# Schematic.net
KiCad netlist of a schematic drawn in Altium Designer
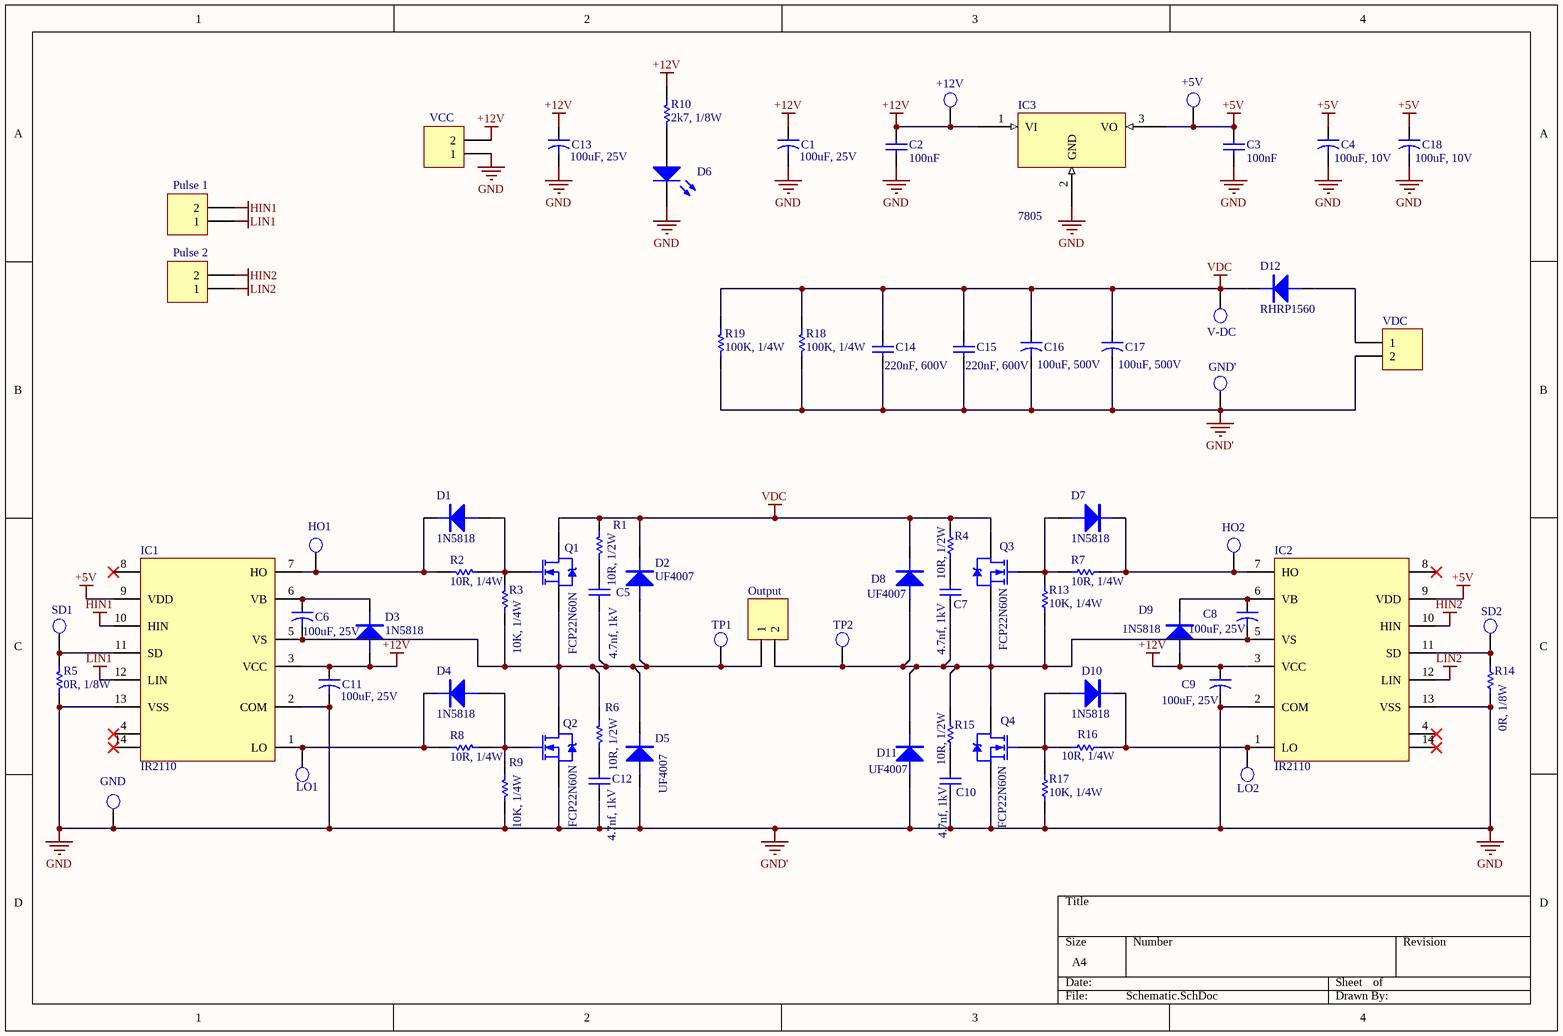
[diagram p0: Schematic.SchDoc]

(export (version "E")
  (design (tool "Eeschema 10.0.6"))
  (components
    (comp (ref "+5V") (value "+5V") (footprint "TPTHD_B_WHT") (libsource (lib "JDEVS-SCH") (part "TP")))
    (comp (ref "+12V") (value "+12V") (footprint "TPTHD_B_WHT") (libsource (lib "JDEVS-SCH") (part "TP")))
    (comp (ref "C1")
      (value "100uF, 25V")
      (footprint "C_EL_6X11")
      (description "200V, 330uF")
      (libsource (lib "Miscellaneous Devices") (part "Cap2"))
    )
    (comp (ref "C2")
      (value "100nF")
      (footprint "C_PLY_6X2_5")
      (description "Capacitor")
      (libsource (lib "Miscellaneous Devices") (part "Cap"))
    )
    (comp (ref "C3")
      (value "100nF")
      (footprint "C_PLY_6X2_5")
      (description "Capacitor")
      (libsource (lib "Miscellaneous Devices") (part "Cap"))
    )
    (comp (ref "C4")
      (value "100uF, 10V")
      (footprint "C_EL_5X11")
      (description "200V, 330uF")
      (libsource (lib "Miscellaneous Devices") (part "Cap2"))
    )
    (comp (ref "C5")
      (value "4.7nf, 1kV")
      (footprint "RAD0.2-1")
      (libsource (lib "Miscellaneous Devices") (part "Cap"))
    )
    (comp (ref "C6")
      (value "100uF, 25V")
      (footprint "C_EL_6X11")
      (description "200V, 330uF")
      (libsource (lib "Miscellaneous Devices") (part "Cap2"))
    )
    (comp (ref "C7")
      (value "4.7nf, 1kV")
      (footprint "RAD0.2-1")
      (libsource (lib "Miscellaneous Devices") (part "Cap"))
    )
    (comp (ref "C8")
      (value "100uF, 25V")
      (footprint "C_EL_6X11")
      (description "200V, 330uF")
      (libsource (lib "") (part "Cap2_1"))
    )
    (comp (ref "C9")
      (value "100uF, 25V")
      (footprint "C_EL_6X11")
      (description "200V, 330uF")
      (libsource (lib "") (part "Cap2_1"))
    )
    (comp (ref "C10")
      (value "4.7nf, 1kV")
      (footprint "RAD0.2-1")
      (libsource (lib "Miscellaneous Devices") (part "Cap"))
    )
    (comp (ref "C11")
      (value "100uF, 25V")
      (footprint "C_EL_6X11")
      (description "200V, 330uF")
      (libsource (lib "Miscellaneous Devices") (part "Cap2"))
    )
    (comp (ref "C12")
      (value "4.7nf, 1kV")
      (footprint "RAD0.2-1")
      (libsource (lib "Miscellaneous Devices") (part "Cap"))
    )
    (comp (ref "C13")
      (value "100uF, 25V")
      (footprint "C_EL_6X11")
      (description "200V, 330uF")
      (libsource (lib "Miscellaneous Devices") (part "Cap2"))
    )
    (comp (ref "C14")
      (value "220nF, 600V")
      (footprint "CAP-pitch15")
      (libsource (lib "Miscellaneous Devices") (part "Cap"))
    )
    (comp (ref "C15")
      (value "220nF, 600V")
      (footprint "CAP-pitch15")
      (libsource (lib "Miscellaneous Devices") (part "Cap"))
    )
    (comp (ref "C16")
      (value "100uF, 500V")
      (footprint "C_EL_18X35")
      (description "500HXW100MEFR18X40")
      (libsource (lib "Miscellaneous Devices") (part "Cap2"))
    )
    (comp (ref "C17")
      (value "100uF, 500V")
      (footprint "C_EL_18X35")
      (description "500HXW100MEFR18X40")
      (libsource (lib "Miscellaneous Devices") (part "Cap2"))
    )
    (comp (ref "C18")
      (value "100uF, 10V")
      (footprint "C_EL_5X11")
      (description "200V, 330uF")
      (libsource (lib "Miscellaneous Devices") (part "Cap2"))
    )
    (comp (ref "D1")
      (value "1N5818")
      (footprint "D_AX04_DO41")
      (fields (field (name "MANUFACTURER") "Comchip Technology"))
      (libsource (lib "JDEVS-SCH") (part "DIODE5"))
    )
    (comp (ref "D2")
      (value "UF4007")
      (footprint "D_AX04_DO41")
      (fields (field (name "MANUFACTURER") "Comchip Technology"))
      (libsource (lib "JDEVS-SCH") (part "DIODE5"))
    )
    (comp (ref "D3")
      (value "1N5818")
      (footprint "D_AX04_DO41")
      (fields (field (name "MANUFACTURER") "Comchip Technology"))
      (libsource (lib "JDEVS-SCH") (part "DIODE5"))
    )
    (comp (ref "D4")
      (value "1N5818")
      (footprint "D_AX04_DO41")
      (fields (field (name "MANUFACTURER") "Comchip Technology"))
      (libsource (lib "JDEVS-SCH") (part "DIODE5"))
    )
    (comp (ref "D5")
      (value "UF4007")
      (footprint "D_AX04_DO41")
      (fields (field (name "MANUFACTURER") "Comchip Technology"))
      (libsource (lib "JDEVS-SCH") (part "DIODE5"))
    )
    (comp (ref "D6")
      (value "LED RED")
      (footprint "LED3MM")
      (description "Typical INFRARED GaAs LED")
      (libsource (lib "Miscellaneous Devices") (part "LED0"))
    )
    (comp (ref "D7")
      (value "1N5818")
      (footprint "D_AX04_DO41")
      (fields (field (name "MANUFACTURER") "Comchip Technology"))
      (libsource (lib "JDEVS-SCH") (part "DIODE5"))
    )
    (comp (ref "D8")
      (value "UF4007")
      (footprint "D_AX04_DO41")
      (fields (field (name "MANUFACTURER") "Comchip Technology"))
      (libsource (lib "JDEVS-SCH") (part "DIODE5"))
    )
    (comp (ref "D9")
      (value "1N5818")
      (footprint "D_AX04_DO41")
      (fields (field (name "MANUFACTURER") "Comchip Technology"))
      (libsource (lib "JDEVS-SCH") (part "DIODE5"))
    )
    (comp (ref "D10")
      (value "1N5818")
      (footprint "D_AX04_DO41")
      (fields (field (name "MANUFACTURER") "Comchip Technology"))
      (libsource (lib "JDEVS-SCH") (part "DIODE5"))
    )
    (comp (ref "D11")
      (value "UF4007")
      (footprint "D_AX04_DO41")
      (fields (field (name "MANUFACTURER") "Comchip Technology"))
      (libsource (lib "JDEVS-SCH") (part "DIODE5"))
    )
    (comp (ref "D12") (value "RHRP1560") (footprint "TO220_21") (libsource (lib "") (part "DIODE5_1")))
    (comp (ref "GND") (value "GND") (footprint "TPTHD_B_WHT") (libsource (lib "JDEVS-SCH") (part "TP")))
    (comp (ref "GND'") (value "HO") (footprint "TPTHD_B_WHT") (libsource (lib "JDEVS-SCH") (part "TP")))
    (comp (ref "HO1") (value "HO") (footprint "TPTHD_B_WHT") (libsource (lib "JDEVS-SCH") (part "TP")))
    (comp (ref "HO2") (value "HO") (footprint "TPTHD_B_WHT") (libsource (lib "JDEVS-SCH") (part "TP")))
    (comp (ref "IC1") (value "IR2110") (footprint "DIP_14") (libsource (lib "") (part "IR2110_1")))
    (comp (ref "IC2") (value "IR2110") (footprint "DIP_14") (libsource (lib "JDEVS-SCH") (part "IR2110")))
    (comp (ref "IC3") (value "7805") (footprint "TO220_3") (libsource (lib "JDEVS-SCH") (part "7805")))
    (comp (ref "LO1") (value "LO") (footprint "TPTHD_B_WHT") (libsource (lib "JDEVS-SCH") (part "TP")))
    (comp (ref "LO2") (value "LO") (footprint "TPTHD_B_WHT") (libsource (lib "JDEVS-SCH") (part "TP")))
    (comp (ref "Output")
      (value "Output")
      (footprint "TBG_2")
      (description "Header, 2-Pin")
      (libsource (lib "") (part "Header 2_1"))
    )
    (comp (ref "Pulse 1")
      (value "~")
      (footprint "TBG_2")
      (description "Header, 2-Pin")
      (libsource (lib "Miscellaneous Connectors") (part "Header 2"))
    )
    (comp (ref "Pulse 2")
      (value "~")
      (footprint "TBG_2")
      (description "Header, 2-Pin")
      (libsource (lib "Miscellaneous Connectors") (part "Header 2"))
    )
    (comp (ref "Q1")
      (value "FCP22N60N")
      (footprint "TO220_32")
      (description "N-Channel Power MOSFET")
      (libsource (lib "Miscellaneous Devices") (part "NMOS-2"))
    )
    (comp (ref "Q2")
      (value "FCP22N60N")
      (footprint "TO220_32")
      (description "N-Channel Power MOSFET")
      (libsource (lib "Miscellaneous Devices") (part "NMOS-2"))
    )
    (comp (ref "Q3")
      (value "FCP22N60N")
      (footprint "TO220_32")
      (description "N-Channel Power MOSFET")
      (libsource (lib "Miscellaneous Devices") (part "NMOS-2"))
    )
    (comp (ref "Q4")
      (value "FCP22N60N")
      (footprint "TO220_32")
      (description "N-Channel Power MOSFET")
      (libsource (lib "Miscellaneous Devices") (part "NMOS-2"))
    )
    (comp (ref "R1")
      (value "10R, 1/2W")
      (footprint "R05W_AX05")
      (description "Resistor")
      (libsource (lib "Miscellaneous Devices") (part "Res1"))
    )
    (comp (ref "R2")
      (value "10R, 1/4W")
      (footprint "R025W_AX04")
      (description "Resistor")
      (libsource (lib "Miscellaneous Devices") (part "Res1"))
    )
    (comp (ref "R3")
      (value "10K, 1/4W")
      (footprint "R025W_AX04")
      (description "Resistor")
      (libsource (lib "Miscellaneous Devices") (part "Res1"))
    )
    (comp (ref "R4")
      (value "10R, 1/2W")
      (footprint "R05W_AX05")
      (description "Resistor")
      (libsource (lib "Miscellaneous Devices") (part "Res1"))
    )
    (comp (ref "R5")
      (value "0R, 1/8W")
      (footprint "R0125W_AX025")
      (description "Resistor")
      (libsource (lib "Miscellaneous Devices") (part "Res1"))
    )
    (comp (ref "R6")
      (value "10R, 1/2W")
      (footprint "R05W_AX05")
      (description "Resistor")
      (libsource (lib "Miscellaneous Devices") (part "Res1"))
    )
    (comp (ref "R7")
      (value "10R, 1/4W")
      (footprint "R025W_AX04")
      (description "Resistor")
      (libsource (lib "Miscellaneous Devices") (part "Res1"))
    )
    (comp (ref "R8")
      (value "10R, 1/4W")
      (footprint "R025W_AX04")
      (description "Resistor")
      (libsource (lib "Miscellaneous Devices") (part "Res1"))
    )
    (comp (ref "R9")
      (value "10K, 1/4W")
      (footprint "R025W_AX04")
      (description "Resistor")
      (libsource (lib "Miscellaneous Devices") (part "Res1"))
    )
    (comp (ref "R10")
      (value "2k7, 1/8W")
      (footprint "R0125W_AX025")
      (description "Resistor")
      (libsource (lib "Miscellaneous Devices") (part "Res1"))
    )
    (comp (ref "R13")
      (value "10K, 1/4W")
      (footprint "R025W_AX04")
      (description "Resistor")
      (libsource (lib "Miscellaneous Devices") (part "Res1"))
    )
    (comp (ref "R14")
      (value "0R, 1/8W")
      (footprint "R0125W_AX025")
      (description "Resistor")
      (libsource (lib "Miscellaneous Devices") (part "Res1"))
    )
    (comp (ref "R15")
      (value "10R, 1/2W")
      (footprint "R05W_AX05")
      (description "Resistor")
      (libsource (lib "Miscellaneous Devices") (part "Res1"))
    )
    (comp (ref "R16")
      (value "10R, 1/4W")
      (footprint "R025W_AX04")
      (description "Resistor")
      (libsource (lib "Miscellaneous Devices") (part "Res1"))
    )
    (comp (ref "R17")
      (value "10K, 1/4W")
      (footprint "R025W_AX04")
      (description "Resistor")
      (libsource (lib "Miscellaneous Devices") (part "Res1"))
    )
    (comp (ref "R18")
      (value "100K, 1/4W")
      (footprint "R025W_AX04")
      (description "Resistor")
      (libsource (lib "Miscellaneous Devices") (part "Res1"))
    )
    (comp (ref "R19")
      (value "100K, 1/4W")
      (footprint "R025W_AX04")
      (description "Resistor")
      (libsource (lib "Miscellaneous Devices") (part "Res1"))
    )
    (comp (ref "SD1") (value "SD") (footprint "TPTHD_B_WHT") (libsource (lib "JDEVS-SCH") (part "TP")))
    (comp (ref "SD2") (value "SD") (footprint "TPTHD_B_WHT") (libsource (lib "JDEVS-SCH") (part "TP")))
    (comp (ref "TP1") (value "HO") (footprint "TPTHD_B_WHT") (libsource (lib "JDEVS-SCH") (part "TP")))
    (comp (ref "TP2") (value "HO") (footprint "TPTHD_B_WHT") (libsource (lib "JDEVS-SCH") (part "TP")))
    (comp (ref "V-DC") (value "HO") (footprint "TPTHD_B_WHT") (libsource (lib "JDEVS-SCH") (part "TP")))
    (comp (ref "VCC")
      (value "~")
      (footprint "TBG_2")
      (description "Header, 2-Pin")
      (libsource (lib "Miscellaneous Connectors") (part "Header 2"))
    )
    (comp (ref "VDC")
      (value "~")
      (footprint "TBG_2")
      (description "Header, 2-Pin")
      (libsource (lib "") (part "Header 2_2"))
    )
  )
  (nets
    (net (code "1") (name "+5V") (class "Default")
      (node (ref "+5V") (pin "1") (pinfunction "1_1") (pintype "passive"))
      (node (ref "C18") (pin "1") (pinfunction "1_1") (pintype "passive"))
      (node (ref "C3") (pin "2") (pinfunction "2_2") (pintype "passive"))
      (node (ref "C4") (pin "1") (pinfunction "1_1") (pintype "passive"))
      (node (ref "IC1") (pin "9") (pinfunction "VDD_9") (pintype "passive"))
      (node (ref "IC2") (pin "9") (pinfunction "VDD_9") (pintype "passive"))
      (node (ref "IC3") (pin "3") (pinfunction "VO_3") (pintype "input"))
    )
    (net (code "2") (name "+12V") (class "Default")
      (node (ref "+12V") (pin "1") (pinfunction "1_1") (pintype "passive"))
      (node (ref "C1") (pin "1") (pinfunction "1_1") (pintype "passive"))
      (node (ref "C11") (pin "1") (pinfunction "1_1") (pintype "passive"))
      (node (ref "C13") (pin "1") (pinfunction "1_1") (pintype "passive"))
      (node (ref "C2") (pin "2") (pinfunction "2_2") (pintype "passive"))
      (node (ref "C9") (pin "1") (pinfunction "1_1") (pintype "passive"))
      (node (ref "D3") (pin "1") (pinfunction "1_1") (pintype "passive"))
      (node (ref "D9") (pin "1") (pinfunction "1_1") (pintype "passive"))
      (node (ref "IC1") (pin "3") (pinfunction "VCC_3") (pintype "passive"))
      (node (ref "IC2") (pin "3") (pinfunction "VCC_3") (pintype "passive"))
      (node (ref "IC3") (pin "1") (pinfunction "VI_1") (pintype "input"))
      (node (ref "R10") (pin "1") (pinfunction "1_1") (pintype "passive"))
      (node (ref "VCC") (pin "2") (pinfunction "2_2") (pintype "passive"))
    )
    (net (code "3") (name "GND") (class "Default")
      (node (ref "C1") (pin "2") (pinfunction "2_2") (pintype "passive"))
      (node (ref "C10") (pin "2") (pinfunction "2_2") (pintype "passive"))
      (node (ref "C11") (pin "2") (pinfunction "2_2") (pintype "passive"))
      (node (ref "C12") (pin "2") (pinfunction "2_2") (pintype "passive"))
      (node (ref "C13") (pin "2") (pinfunction "2_2") (pintype "passive"))
      (node (ref "C14") (pin "2") (pinfunction "2_2") (pintype "passive"))
      (node (ref "C15") (pin "2") (pinfunction "2_2") (pintype "passive"))
      (node (ref "C16") (pin "2") (pinfunction "2_2") (pintype "passive"))
      (node (ref "C17") (pin "2") (pinfunction "2_2") (pintype "passive"))
      (node (ref "C18") (pin "2") (pinfunction "2_2") (pintype "passive"))
      (node (ref "C2") (pin "1") (pinfunction "1_1") (pintype "passive"))
      (node (ref "C3") (pin "1") (pinfunction "1_1") (pintype "passive"))
      (node (ref "C4") (pin "2") (pinfunction "2_2") (pintype "passive"))
      (node (ref "C9") (pin "2") (pinfunction "2_2") (pintype "passive"))
      (node (ref "D11") (pin "1") (pinfunction "1_1") (pintype "passive"))
      (node (ref "D5") (pin "1") (pinfunction "1_1") (pintype "passive"))
      (node (ref "D6") (pin "2") (pinfunction "K_2") (pintype "passive"))
      (node (ref "GND") (pin "1") (pinfunction "1_1") (pintype "passive"))
      (node (ref "GND'") (pin "1") (pinfunction "1_1") (pintype "passive"))
      (node (ref "IC1") (pin "13") (pinfunction "VSS_13") (pintype "passive"))
      (node (ref "IC1") (pin "2") (pinfunction "COM_2") (pintype "passive"))
      (node (ref "IC2") (pin "13") (pinfunction "VSS_13") (pintype "passive"))
      (node (ref "IC2") (pin "2") (pinfunction "COM_2") (pintype "passive"))
      (node (ref "IC3") (pin "2") (pinfunction "GND_2") (pintype "input"))
      (node (ref "Q2") (pin "3") (pinfunction "S_3") (pintype "passive"))
      (node (ref "Q4") (pin "3") (pinfunction "S_3") (pintype "passive"))
      (node (ref "R14") (pin "1") (pinfunction "1_1") (pintype "passive"))
      (node (ref "R17") (pin "2") (pinfunction "2_2") (pintype "passive"))
      (node (ref "R18") (pin "1") (pinfunction "1_1") (pintype "passive"))
      (node (ref "R19") (pin "1") (pinfunction "1_1") (pintype "passive"))
      (node (ref "R5") (pin "1") (pinfunction "1_1") (pintype "passive"))
      (node (ref "R9") (pin "2") (pinfunction "2_2") (pintype "passive"))
      (node (ref "VCC") (pin "1") (pinfunction "1_1") (pintype "passive"))
      (node (ref "VDC") (pin "2") (pinfunction "2_2") (pintype "passive"))
    )
    (net (code "4") (name "HIN1") (class "Default")
      (node (ref "IC1") (pin "10") (pinfunction "HIN_10") (pintype "passive"))
      (node (ref "Pulse 1") (pin "2") (pinfunction "2_2") (pintype "passive"))
    )
    (net (code "5") (name "HIN2") (class "Default")
      (node (ref "IC2") (pin "10") (pinfunction "HIN_10") (pintype "passive"))
      (node (ref "Pulse 2") (pin "2") (pinfunction "2_2") (pintype "passive"))
    )
    (net (code "6") (name "LIN1") (class "Default")
      (node (ref "IC1") (pin "12") (pinfunction "LIN_12") (pintype "power_in"))
      (node (ref "Pulse 1") (pin "1") (pinfunction "1_1") (pintype "passive"))
    )
    (net (code "7") (name "LIN2") (class "Default")
      (node (ref "IC2") (pin "12") (pinfunction "LIN_12") (pintype "power_in"))
      (node (ref "Pulse 2") (pin "1") (pinfunction "1_1") (pintype "passive"))
    )
    (net (code "8") (name "Net-(C5-Pad1)") (class "Default")
      (node (ref "C5") (pin "1") (pinfunction "1_1") (pintype "passive"))
      (node (ref "R1") (pin "2") (pinfunction "2_2") (pintype "passive"))
    )
    (net (code "9") (name "Net-(C7-Pad1)") (class "Default")
      (node (ref "C7") (pin "1") (pinfunction "1_1") (pintype "passive"))
      (node (ref "R4") (pin "2") (pinfunction "2_2") (pintype "passive"))
    )
    (net (code "10") (name "Net-(C10-Pad1)") (class "Default")
      (node (ref "C10") (pin "1") (pinfunction "1_1") (pintype "passive"))
      (node (ref "R15") (pin "2") (pinfunction "2_2") (pintype "passive"))
    )
    (net (code "11") (name "Net-(C12-Pad1)") (class "Default")
      (node (ref "C12") (pin "1") (pinfunction "1_1") (pintype "passive"))
      (node (ref "R6") (pin "2") (pinfunction "2_2") (pintype "passive"))
    )
    (net (code "12") (name "Net-(D6-A)") (class "Default")
      (node (ref "D6") (pin "1") (pinfunction "A_1") (pintype "passive"))
      (node (ref "R10") (pin "2") (pinfunction "2_2") (pintype "passive"))
    )
    (net (code "13") (name "Net-(D12-1)") (class "Default")
      (node (ref "D12") (pin "2") (pinfunction "1_2") (pintype "passive"))
      (node (ref "VDC") (pin "1") (pinfunction "1_1") (pintype "passive"))
    )
    (net (code "14") (name "Net-(IC1-HO)") (class "Default")
      (node (ref "D1") (pin "2") (pinfunction "2_2") (pintype "passive"))
      (node (ref "HO1") (pin "1") (pinfunction "1_1") (pintype "passive"))
      (node (ref "IC1") (pin "7") (pinfunction "HO_7") (pintype "passive"))
      (node (ref "R2") (pin "1") (pinfunction "1_1") (pintype "passive"))
    )
    (net (code "15") (name "Net-(IC1-LO)") (class "Default")
      (node (ref "D4") (pin "2") (pinfunction "2_2") (pintype "passive"))
      (node (ref "IC1") (pin "1") (pinfunction "LO_1") (pintype "passive"))
      (node (ref "LO1") (pin "1") (pinfunction "1_1") (pintype "passive"))
      (node (ref "R8") (pin "1") (pinfunction "1_1") (pintype "passive"))
    )
    (net (code "16") (name "Net-(IC1-SD)") (class "Default")
      (node (ref "IC1") (pin "11") (pinfunction "SD_11") (pintype "power_in"))
      (node (ref "R5") (pin "2") (pinfunction "2_2") (pintype "passive"))
      (node (ref "SD1") (pin "1") (pinfunction "1_1") (pintype "passive"))
    )
    (net (code "17") (name "Net-(IC1-VB)") (class "Default")
      (node (ref "C6") (pin "1") (pinfunction "1_1") (pintype "passive"))
      (node (ref "D3") (pin "2") (pinfunction "2_2") (pintype "passive"))
      (node (ref "IC1") (pin "6") (pinfunction "VB_6") (pintype "passive"))
    )
    (net (code "18") (name "Net-(IC1-VS)") (class "Default")
      (node (ref "C5") (pin "2") (pinfunction "2_2") (pintype "passive"))
      (node (ref "C6") (pin "2") (pinfunction "2_2") (pintype "passive"))
      (node (ref "D2") (pin "1") (pinfunction "1_1") (pintype "passive"))
      (node (ref "D5") (pin "2") (pinfunction "2_2") (pintype "passive"))
      (node (ref "IC1") (pin "5") (pinfunction "VS_5") (pintype "passive"))
      (node (ref "Output") (pin "1") (pinfunction "1_1") (pintype "passive"))
      (node (ref "Q1") (pin "3") (pinfunction "S_3") (pintype "passive"))
      (node (ref "Q2") (pin "2") (pinfunction "D_2") (pintype "passive"))
      (node (ref "R3") (pin "2") (pinfunction "2_2") (pintype "passive"))
      (node (ref "R6") (pin "1") (pinfunction "1_1") (pintype "passive"))
      (node (ref "TP1") (pin "1") (pinfunction "1_1") (pintype "passive"))
    )
    (net (code "19") (name "Net-(IC2-HO)") (class "Default")
      (node (ref "D7") (pin "2") (pinfunction "2_2") (pintype "passive"))
      (node (ref "HO2") (pin "1") (pinfunction "1_1") (pintype "passive"))
      (node (ref "IC2") (pin "7") (pinfunction "HO_7") (pintype "passive"))
      (node (ref "R7") (pin "1") (pinfunction "1_1") (pintype "passive"))
    )
    (net (code "20") (name "Net-(IC2-LO)") (class "Default")
      (node (ref "D10") (pin "2") (pinfunction "2_2") (pintype "passive"))
      (node (ref "IC2") (pin "1") (pinfunction "LO_1") (pintype "passive"))
      (node (ref "LO2") (pin "1") (pinfunction "1_1") (pintype "passive"))
      (node (ref "R16") (pin "1") (pinfunction "1_1") (pintype "passive"))
    )
    (net (code "21") (name "Net-(IC2-SD)") (class "Default")
      (node (ref "IC2") (pin "11") (pinfunction "SD_11") (pintype "power_in"))
      (node (ref "R14") (pin "2") (pinfunction "2_2") (pintype "passive"))
      (node (ref "SD2") (pin "1") (pinfunction "1_1") (pintype "passive"))
    )
    (net (code "22") (name "Net-(IC2-VB)") (class "Default")
      (node (ref "C8") (pin "1") (pinfunction "1_1") (pintype "passive"))
      (node (ref "D9") (pin "2") (pinfunction "2_2") (pintype "passive"))
      (node (ref "IC2") (pin "6") (pinfunction "VB_6") (pintype "passive"))
    )
    (net (code "23") (name "Net-(IC2-VS)") (class "Default")
      (node (ref "C7") (pin "2") (pinfunction "2_2") (pintype "passive"))
      (node (ref "C8") (pin "2") (pinfunction "2_2") (pintype "passive"))
      (node (ref "D11") (pin "2") (pinfunction "2_2") (pintype "passive"))
      (node (ref "D8") (pin "1") (pinfunction "1_1") (pintype "passive"))
      (node (ref "IC2") (pin "5") (pinfunction "VS_5") (pintype "passive"))
      (node (ref "Output") (pin "2") (pinfunction "2_2") (pintype "passive"))
      (node (ref "Q3") (pin "3") (pinfunction "S_3") (pintype "passive"))
      (node (ref "Q4") (pin "2") (pinfunction "D_2") (pintype "passive"))
      (node (ref "R13") (pin "2") (pinfunction "2_2") (pintype "passive"))
      (node (ref "R15") (pin "1") (pinfunction "1_1") (pintype "passive"))
      (node (ref "TP2") (pin "1") (pinfunction "1_1") (pintype "passive"))
    )
    (net (code "24") (name "Net-(Q1-G)") (class "Default")
      (node (ref "D1") (pin "1") (pinfunction "1_1") (pintype "passive"))
      (node (ref "Q1") (pin "1") (pinfunction "G_1") (pintype "passive"))
      (node (ref "R2") (pin "2") (pinfunction "2_2") (pintype "passive"))
      (node (ref "R3") (pin "1") (pinfunction "1_1") (pintype "passive"))
    )
    (net (code "25") (name "Net-(Q2-G)") (class "Default")
      (node (ref "D4") (pin "1") (pinfunction "1_1") (pintype "passive"))
      (node (ref "Q2") (pin "1") (pinfunction "G_1") (pintype "passive"))
      (node (ref "R8") (pin "2") (pinfunction "2_2") (pintype "passive"))
      (node (ref "R9") (pin "1") (pinfunction "1_1") (pintype "passive"))
    )
    (net (code "26") (name "Net-(Q3-G)") (class "Default")
      (node (ref "D7") (pin "1") (pinfunction "1_1") (pintype "passive"))
      (node (ref "Q3") (pin "1") (pinfunction "G_1") (pintype "passive"))
      (node (ref "R13") (pin "1") (pinfunction "1_1") (pintype "passive"))
      (node (ref "R7") (pin "2") (pinfunction "2_2") (pintype "passive"))
    )
    (net (code "27") (name "Net-(Q4-G)") (class "Default")
      (node (ref "D10") (pin "1") (pinfunction "1_1") (pintype "passive"))
      (node (ref "Q4") (pin "1") (pinfunction "G_1") (pintype "passive"))
      (node (ref "R16") (pin "2") (pinfunction "2_2") (pintype "passive"))
      (node (ref "R17") (pin "1") (pinfunction "1_1") (pintype "passive"))
    )
    (net (code "28") (name "VDC") (class "Default")
      (node (ref "C14") (pin "1") (pinfunction "1_1") (pintype "passive"))
      (node (ref "C15") (pin "1") (pinfunction "1_1") (pintype "passive"))
      (node (ref "C16") (pin "1") (pinfunction "1_1") (pintype "passive"))
      (node (ref "C17") (pin "1") (pinfunction "1_1") (pintype "passive"))
      (node (ref "D12") (pin "1") (pinfunction "2_1") (pintype "passive"))
      (node (ref "D2") (pin "2") (pinfunction "2_2") (pintype "passive"))
      (node (ref "D8") (pin "2") (pinfunction "2_2") (pintype "passive"))
      (node (ref "Q1") (pin "2") (pinfunction "D_2") (pintype "passive"))
      (node (ref "Q3") (pin "2") (pinfunction "D_2") (pintype "passive"))
      (node (ref "R1") (pin "1") (pinfunction "1_1") (pintype "passive"))
      (node (ref "R18") (pin "2") (pinfunction "2_2") (pintype "passive"))
      (node (ref "R19") (pin "2") (pinfunction "2_2") (pintype "passive"))
      (node (ref "R4") (pin "1") (pinfunction "1_1") (pintype "passive"))
      (node (ref "V-DC") (pin "1") (pinfunction "1_1") (pintype "passive"))
    )
    (net (code "29") (name "unconnected-(IC1-Pad4)") (class "Default")
      (node (ref "IC1") (pin "4") (pintype "passive+no_connect"))
    )
    (net (code "30") (name "unconnected-(IC1-Pad8)") (class "Default")
      (node (ref "IC1") (pin "8") (pintype "power_in+no_connect"))
    )
    (net (code "31") (name "unconnected-(IC1-Pad14)") (class "Default")
      (node (ref "IC1") (pin "14") (pintype "passive+no_connect"))
    )
    (net (code "32") (name "unconnected-(IC2-Pad4)") (class "Default")
      (node (ref "IC2") (pin "4") (pintype "passive+no_connect"))
    )
    (net (code "33") (name "unconnected-(IC2-Pad8)") (class "Default")
      (node (ref "IC2") (pin "8") (pintype "power_in+no_connect"))
    )
    (net (code "34") (name "unconnected-(IC2-Pad14)") (class "Default")
      (node (ref "IC2") (pin "14") (pintype "passive+no_connect"))
    )
  )
)
